# Prototype_V1.net
KiCad netlist of a schematic drawn in Altium Designer
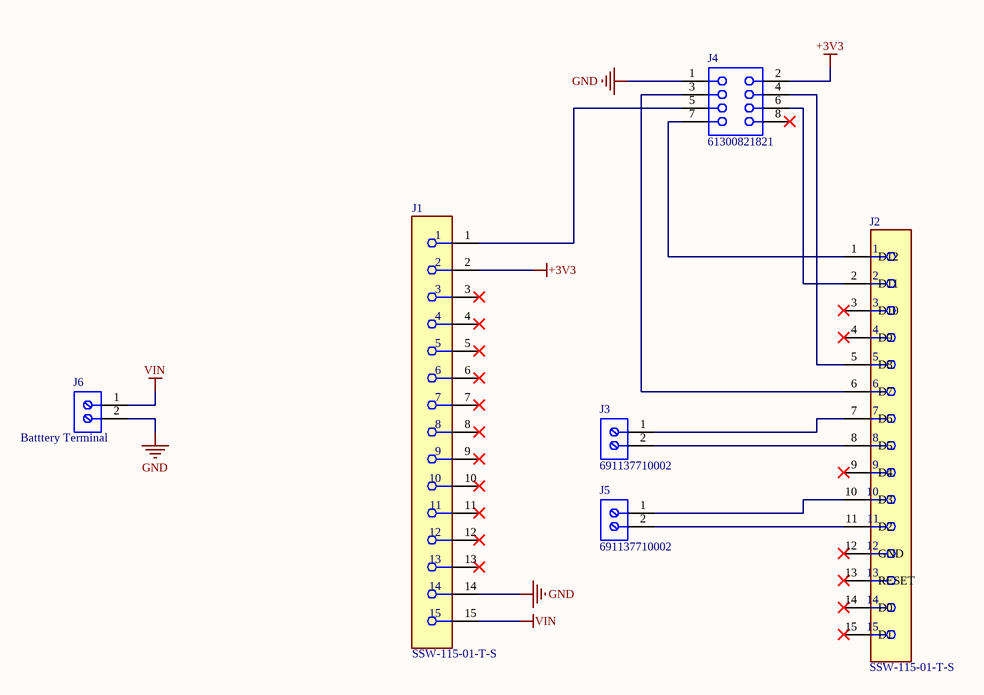
[diagram p0: Prototype V1.SchDoc]

(export (version "E")
  (design (tool "Eeschema 10.0.6"))
  (components
    (comp (ref "J1")
      (value "SSW-115-01-T-S")
      (footprint "FP-SSW-115-01-T-S-MFG")
      (description "CONN RCPT 15POS 0.1 TIN PCB")
      (libsource (lib "Altium Content Vault") (part "de2cdd76613f87adcba81301aaab7e9"))
    )
    (comp (ref "J2")
      (value "SSW-115-01-T-S")
      (footprint "FP-SSW-115-01-T-S-MFG")
      (description "CONN RCPT 15POS 0.1 TIN PCB")
      (libsource (lib "") (part "de2cdd76613f87adcba81301aaab7e9_1"))
    )
    (comp (ref "J3")
      (value "691137710002")
      (footprint "691137710002")
      (libsource (lib "Altium Content Vault") (part "TBL - 1R - 02P - Screw"))
    )
    (comp (ref "J4")
      (value "61300821821")
      (footprint "61300821821")
      (libsource (lib "Altium Content Vault") (part "Header_Female_2R_08P"))
    )
    (comp (ref "J5")
      (value "691137710002")
      (footprint "691137710002")
      (libsource (lib "Altium Content Vault") (part "TBL - 1R - 02P - Screw"))
    )
    (comp (ref "J6")
      (value "Batttery Terminal")
      (footprint "691137710002")
      (libsource (lib "Altium Content Vault") (part "TBL - 1R - 02P - Screw"))
    )
  )
  (nets
    (net (code "1") (name "+3V3") (class "Default")
      (node (ref "J1") (pin "2") (pinfunction "2_2") (pintype "passive"))
      (node (ref "J4") (pin "2") (pinfunction "2_2") (pintype "passive"))
    )
    (net (code "2") (name "GND") (class "Default")
      (node (ref "J1") (pin "14") (pinfunction "14_14") (pintype "passive"))
      (node (ref "J4") (pin "1") (pinfunction "1_1") (pintype "passive"))
      (node (ref "J6") (pin "2") (pinfunction "2_2") (pintype "passive"))
    )
    (net (code "3") (name "Net-(J1-Pad1)") (class "Default")
      (node (ref "J1") (pin "1") (pinfunction "1_1") (pintype "passive"))
      (node (ref "J4") (pin "5") (pinfunction "5_5") (pintype "passive"))
    )
    (net (code "4") (name "Net-(J2-D2)") (class "Default")
      (node (ref "J2") (pin "11") (pinfunction "D2_11") (pintype "passive"))
      (node (ref "J5") (pin "2") (pinfunction "2_2") (pintype "passive"))
    )
    (net (code "5") (name "Net-(J2-D3)") (class "Default")
      (node (ref "J2") (pin "10") (pinfunction "D3_10") (pintype "passive"))
      (node (ref "J5") (pin "1") (pinfunction "1_1") (pintype "passive"))
    )
    (net (code "6") (name "Net-(J2-D5)") (class "Default")
      (node (ref "J2") (pin "8") (pinfunction "D5_8") (pintype "passive"))
      (node (ref "J3") (pin "2") (pinfunction "2_2") (pintype "passive"))
    )
    (net (code "7") (name "Net-(J2-D6)") (class "Default")
      (node (ref "J2") (pin "7") (pinfunction "D6_7") (pintype "passive"))
      (node (ref "J3") (pin "1") (pinfunction "1_1") (pintype "passive"))
    )
    (net (code "8") (name "Net-(J2-D7)") (class "Default")
      (node (ref "J2") (pin "6") (pinfunction "D7_6") (pintype "passive"))
      (node (ref "J4") (pin "3") (pinfunction "3_3") (pintype "passive"))
    )
    (net (code "9") (name "Net-(J2-D8)") (class "Default")
      (node (ref "J2") (pin "5") (pinfunction "D8_5") (pintype "passive"))
      (node (ref "J4") (pin "4") (pinfunction "4_4") (pintype "passive"))
    )
    (net (code "10") (name "Net-(J2-D11)") (class "Default")
      (node (ref "J2") (pin "2") (pinfunction "D11_2") (pintype "passive"))
      (node (ref "J4") (pin "6") (pinfunction "6_6") (pintype "passive"))
    )
    (net (code "11") (name "Net-(J2-D12)") (class "Default")
      (node (ref "J2") (pin "1") (pinfunction "D12_1") (pintype "passive"))
      (node (ref "J4") (pin "7") (pinfunction "7_7") (pintype "passive"))
    )
    (net (code "12") (name "VIN") (class "Default")
      (node (ref "J1") (pin "15") (pinfunction "15_15") (pintype "passive"))
      (node (ref "J6") (pin "1") (pinfunction "1_1") (pintype "passive"))
    )
    (net (code "13") (name "unconnected-(J1-Pad3)") (class "Default")
      (node (ref "J1") (pin "3") (pinfunction "3_3") (pintype "passive+no_connect"))
    )
    (net (code "14") (name "unconnected-(J1-Pad4)") (class "Default")
      (node (ref "J1") (pin "4") (pinfunction "4_4") (pintype "passive+no_connect"))
    )
    (net (code "15") (name "unconnected-(J1-Pad5)") (class "Default")
      (node (ref "J1") (pin "5") (pinfunction "5_5") (pintype "passive+no_connect"))
    )
    (net (code "16") (name "unconnected-(J1-Pad6)") (class "Default")
      (node (ref "J1") (pin "6") (pinfunction "6_6") (pintype "passive+no_connect"))
    )
    (net (code "17") (name "unconnected-(J1-Pad7)") (class "Default")
      (node (ref "J1") (pin "7") (pinfunction "7_7") (pintype "passive+no_connect"))
    )
    (net (code "18") (name "unconnected-(J1-Pad8)") (class "Default")
      (node (ref "J1") (pin "8") (pinfunction "8_8") (pintype "passive+no_connect"))
    )
    (net (code "19") (name "unconnected-(J1-Pad9)") (class "Default")
      (node (ref "J1") (pin "9") (pinfunction "9_9") (pintype "passive+no_connect"))
    )
    (net (code "20") (name "unconnected-(J1-Pad10)") (class "Default")
      (node (ref "J1") (pin "10") (pinfunction "10_10") (pintype "passive+no_connect"))
    )
    (net (code "21") (name "unconnected-(J1-Pad11)") (class "Default")
      (node (ref "J1") (pin "11") (pinfunction "11_11") (pintype "passive+no_connect"))
    )
    (net (code "22") (name "unconnected-(J1-Pad12)") (class "Default")
      (node (ref "J1") (pin "12") (pinfunction "12_12") (pintype "passive+no_connect"))
    )
    (net (code "23") (name "unconnected-(J1-Pad13)") (class "Default")
      (node (ref "J1") (pin "13") (pinfunction "13_13") (pintype "passive+no_connect"))
    )
    (net (code "24") (name "unconnected-(J2-D0-Pad14)") (class "Default")
      (node (ref "J2") (pin "14") (pinfunction "D0_14") (pintype "passive+no_connect"))
    )
    (net (code "25") (name "unconnected-(J2-D1-Pad15)") (class "Default")
      (node (ref "J2") (pin "15") (pinfunction "D1_15") (pintype "passive+no_connect"))
    )
    (net (code "26") (name "unconnected-(J2-D4-Pad9)") (class "Default")
      (node (ref "J2") (pin "9") (pinfunction "D4_9") (pintype "passive+no_connect"))
    )
    (net (code "27") (name "unconnected-(J2-D9-Pad4)") (class "Default")
      (node (ref "J2") (pin "4") (pinfunction "D9_4") (pintype "passive+no_connect"))
    )
    (net (code "28") (name "unconnected-(J2-D10-Pad3)") (class "Default")
      (node (ref "J2") (pin "3") (pinfunction "D10_3") (pintype "passive+no_connect"))
    )
    (net (code "29") (name "unconnected-(J2-GND-Pad12)") (class "Default")
      (node (ref "J2") (pin "12") (pinfunction "GND_12") (pintype "passive+no_connect"))
    )
    (net (code "30") (name "unconnected-(J2-RESET-Pad13)") (class "Default")
      (node (ref "J2") (pin "13") (pinfunction "RESET_13") (pintype "passive+no_connect"))
    )
    (net (code "31") (name "unconnected-(J4-Pad8)") (class "Default")
      (node (ref "J4") (pin "8") (pinfunction "8_8") (pintype "passive+no_connect"))
    )
  )
)
